# PCBPayloadV7.net
KiCad netlist of a schematic drawn in EAGLE
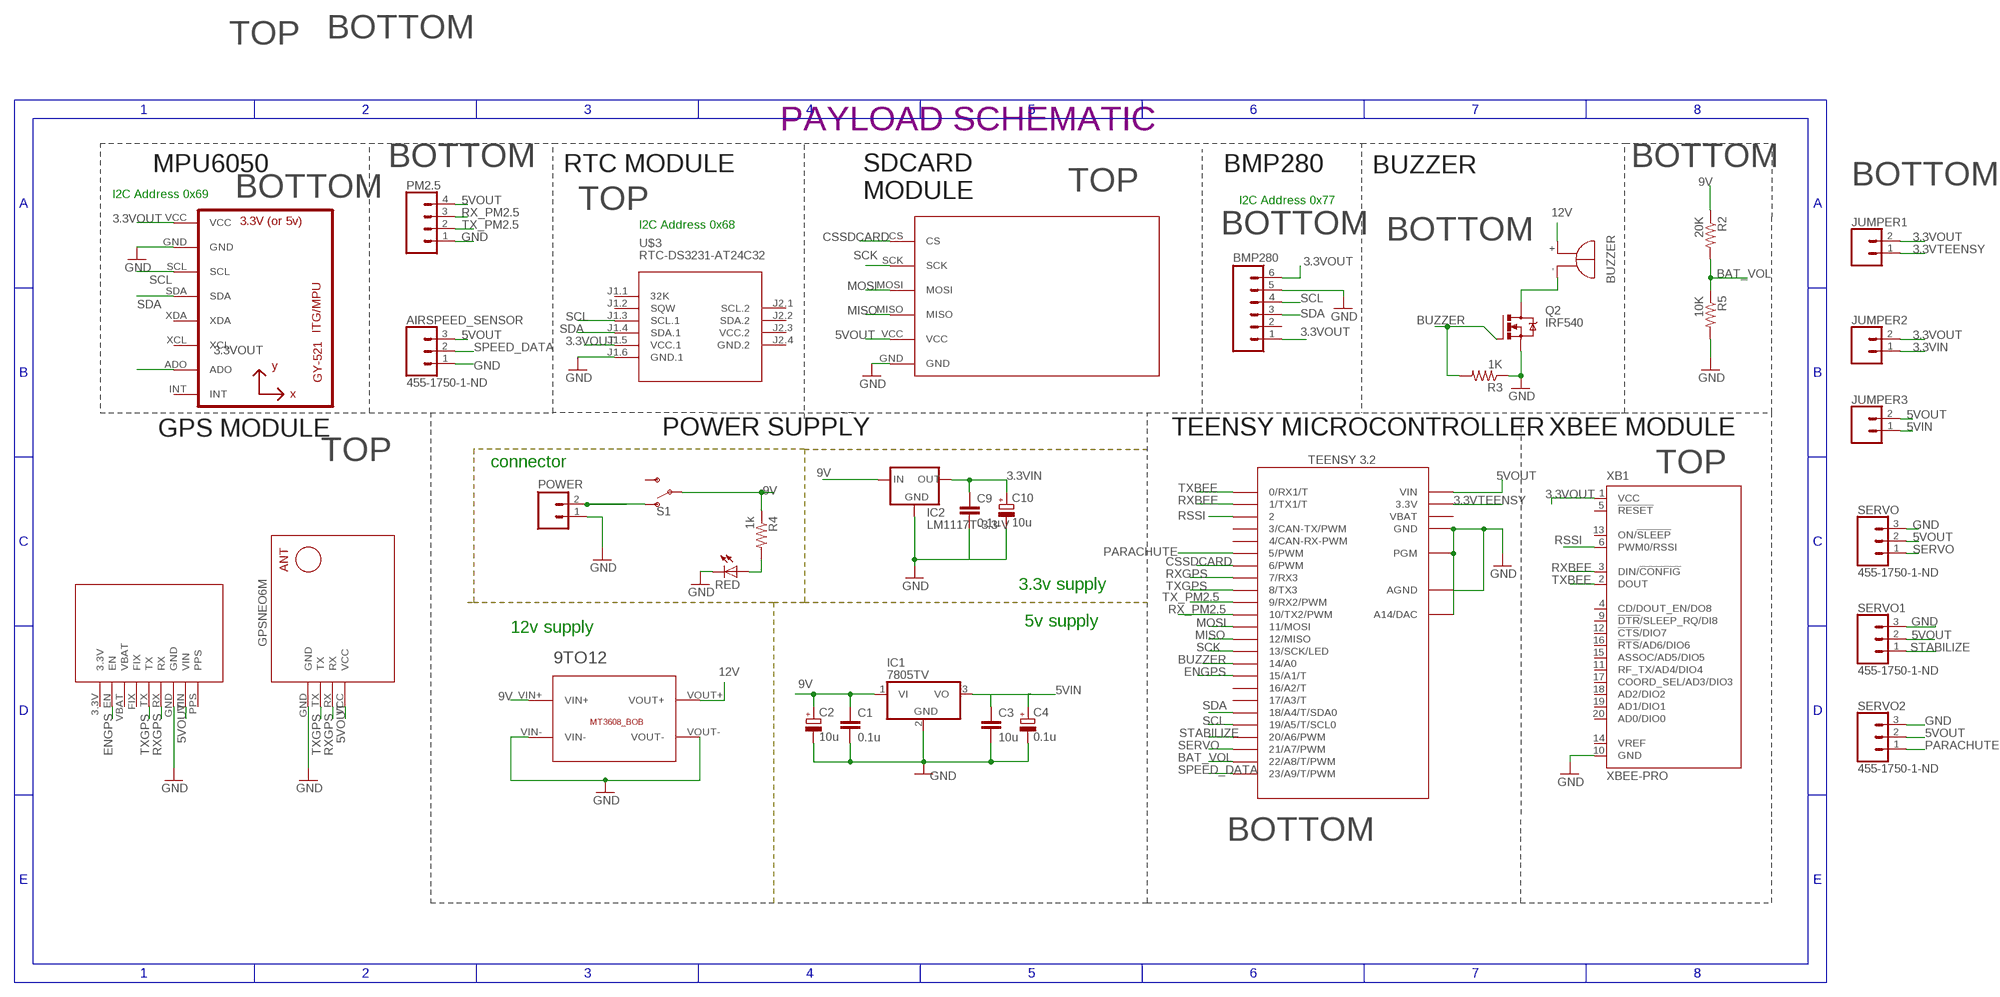
[diagram p0: schematic, sheet 1]

(export (version "E")
  (design (tool "Eeschema 10.0.6"))
  (components
    (comp (ref "9TO12")
      (value "BREAKOUTS_MT3608_BOB")
      (footprint "eagle-import:BREAKOUTS_MT3608_BOB")
      (libsource (lib "eagle-import") (part "BREAKOUTS_MT3608_BOB"))
    )
    (comp (ref "AIRSPEED_SENSOR")
      (value "455-1750-1-ND")
      (footprint "eagle-import:1X03")
      (libsource (lib "eagle-import") (part "CONN_03"))
    )
    (comp (ref "BMP280")
      (value "M06")
      (footprint "eagle-import:06P")
      (libsource (lib "eagle-import") (part "M06"))
    )
    (comp (ref "C1")
      (value "0.1u")
      (footprint "eagle-import:C025-025X050")
      (libsource (lib "eagle-import") (part "C-EU025-025X050"))
    )
    (comp (ref "C2")
      (value "10u")
      (footprint "eagle-import:E2,5-6")
      (libsource (lib "eagle-import") (part "CPOL-EUE2.5-6"))
    )
    (comp (ref "C3")
      (value "10u")
      (footprint "eagle-import:C025-025X050")
      (libsource (lib "eagle-import") (part "C-EU025-025X050"))
    )
    (comp (ref "C4")
      (value "0.1u")
      (footprint "eagle-import:E2,5-6")
      (libsource (lib "eagle-import") (part "CPOL-EUE2.5-6"))
    )
    (comp (ref "C9")
      (value "0.1u")
      (footprint "eagle-import:C025-025X050")
      (libsource (lib "eagle-import") (part "C-EU025-025X050"))
    )
    (comp (ref "C10")
      (value "10u")
      (footprint "eagle-import:E2,5-6")
      (libsource (lib "eagle-import") (part "CPOL-EUE2.5-6"))
    )
    (comp (ref "IC1")
      (value "7805TV")
      (footprint "eagle-import:TO220V")
      (libsource (lib "eagle-import") (part "78TV05"))
    )
    (comp (ref "IC2")
      (value "LM1117T-3.3-V")
      (footprint "eagle-import:TO220V")
      (libsource (lib "eagle-import") (part "LM1117T--V3.3"))
    )
    (comp (ref "JUMPER1")
      (value "CONN_02")
      (footprint "eagle-import:1X02")
      (libsource (lib "eagle-import") (part "CONN_02"))
    )
    (comp (ref "JUMPER2")
      (value "CONN_02")
      (footprint "eagle-import:1X02")
      (libsource (lib "eagle-import") (part "CONN_02"))
    )
    (comp (ref "JUMPER3")
      (value "CONN_02")
      (footprint "eagle-import:1X02")
      (libsource (lib "eagle-import") (part "CONN_02"))
    )
    (comp (ref "PM2.5")
      (value "CONN_04")
      (footprint "eagle-import:1X04")
      (libsource (lib "eagle-import") (part "CONN_04"))
    )
    (comp (ref "POWER")
      (value "CEDT_JANUARY_2015_V5_M02")
      (footprint "eagle-import:CEDT_JANUARY_2015_V5_02P")
      (libsource (lib "eagle-import") (part "CEDT_JANUARY_2015_V5_M02"))
    )
    (comp (ref "Q2")
      (value "IRF540")
      (footprint "eagle-import:TO220BV")
      (libsource (lib "eagle-import") (part "IRF540"))
    )
    (comp (ref "R2")
      (value "20K")
      (footprint "eagle-import:0204_7")
      (libsource (lib "eagle-import") (part "R-US_0204/7"))
    )
    (comp (ref "R3")
      (value "1K")
      (footprint "eagle-import:0204_7")
      (libsource (lib "eagle-import") (part "R-US_0204/7"))
    )
    (comp (ref "R4")
      (value "1k")
      (footprint "eagle-import:0204_7")
      (libsource (lib "eagle-import") (part "R-US_0204/7"))
    )
    (comp (ref "R5")
      (value "10K")
      (footprint "eagle-import:0204_7")
      (libsource (lib "eagle-import") (part "R-US_0204/7"))
    )
    (comp (ref "RED")
      (value "red")
      (footprint "eagle-import:LED3MM")
      (libsource (lib "eagle-import") (part "LED3MM"))
    )
    (comp (ref "S1")
      (value "SWITCH-SPDT-PTH-11.6X4.0MM")
      (footprint "eagle-import:SWITCH_SPDT_PTH_11.6X4.0MM")
      (libsource (lib "eagle-import") (part "SWITCH-SPDT-PTH-11.6X4.0MM"))
    )
    (comp (ref "SERVO")
      (value "455-1750-1-ND")
      (footprint "eagle-import:1X03")
      (libsource (lib "eagle-import") (part "CONN_03"))
    )
    (comp (ref "SERVO1")
      (value "455-1750-1-ND")
      (footprint "eagle-import:1X03")
      (libsource (lib "eagle-import") (part "CONN_03"))
    )
    (comp (ref "SERVO2")
      (value "455-1750-1-ND")
      (footprint "eagle-import:1X03")
      (libsource (lib "eagle-import") (part "CONN_03"))
    )
    (comp (ref "SG1")
      (value "BUZZER_EB2209A")
      (footprint "eagle-import:BUZZER_EB2209A")
      (libsource (lib "eagle-import") (part "BUZZER_EB2209A"))
    )
    (comp (ref "U$1")
      (value "GPS-RECEIVER-NEO6M")
      (footprint "eagle-import:GPS-RECEIVER-NEO6M")
      (libsource (lib "eagle-import") (part "GPS-RECEIVER-NEO6M"))
    )
    (comp (ref "U$2")
      (value "TEENSY_3.1-3.2_OUTER_ROW")
      (footprint "eagle-import:TEENSY_3.0-3.2&LC_OUTER_ROW")
      (libsource (lib "eagle-import") (part "TEENSY_3.1-3.2_OUTER_ROW"))
    )
    (comp (ref "U$3")
      (value "RTC-DS3231-AT24C32")
      (footprint "eagle-import:RTC-DS3231-AT24C32")
      (libsource (lib "eagle-import") (part "RTC-DS3231-AT24C32"))
    )
    (comp (ref "U$4")
      (value "ADAFRUIT_GPS")
      (footprint "eagle-import:ADAFRUIT_GPS")
      (libsource (lib "eagle-import") (part "ADAFRUIT_GPS"))
    )
    (comp (ref "U$5")
      (value "SDCARD")
      (footprint "eagle-import:M0SDCARDMODULE")
      (libsource (lib "eagle-import") (part "SDCARD"))
    )
    (comp (ref "U1")
      (value "GY-521MPU6050")
      (footprint "eagle-import:GY-521")
      (libsource (lib "eagle-import") (part "GY-521MPU6050"))
    )
    (comp (ref "XB1")
      (value "XBEE-PRO")
      (footprint "eagle-import:XBEE-PRO")
      (fields (field (name "MPN") "XBP24-AWI-001"))
      (libsource (lib "eagle-import") (part "XBEE-PRO"))
    )
  )
  (nets
    (net (code "1") (name "/3.3VIN") (class "Default")
      (node (ref "C10") (pin "+") (pinfunction "+_+") (pintype "passive"))
      (node (ref "C9") (pin "1") (pinfunction "1_1") (pintype "passive"))
      (node (ref "IC2") (pin "2") (pinfunction "OUT_2") (pintype "passive"))
      (node (ref "JUMPER2") (pin "1") (pinfunction "1_1") (pintype "passive"))
    )
    (net (code "2") (name "/3.3VOUT") (class "Default")
      (node (ref "BMP280") (pin "1") (pinfunction "1_1") (pintype "passive"))
      (node (ref "BMP280") (pin "6") (pinfunction "6_6") (pintype "passive"))
      (node (ref "JUMPER1") (pin "2") (pinfunction "2_2") (pintype "passive"))
      (node (ref "JUMPER2") (pin "2") (pinfunction "2_2") (pintype "passive"))
      (node (ref "U$3") (pin "J1.5") (pinfunction "VCC.1_J1.5") (pintype "power_in"))
      (node (ref "U1") (pin "ADO") (pinfunction "ADO_ADO") (pintype "bidirectional"))
      (node (ref "U1") (pin "VCC") (pinfunction "VCC_VCC") (pintype "bidirectional"))
      (node (ref "XB1") (pin "1") (pinfunction "VCC_1") (pintype "power_in"))
    )
    (net (code "3") (name "/3.3VTEENSY") (class "Default")
      (node (ref "JUMPER1") (pin "1") (pinfunction "1_1") (pintype "passive"))
      (node (ref "U$2") (pin "3.3V") (pinfunction "3.3V_3.3V") (pintype "power_in"))
      (node (ref "U$2") (pin "3.3V1") (pinfunction "3.3V_3.3V1") (pintype "power_in"))
    )
    (net (code "4") (name "/5VIN") (class "Default")
      (node (ref "C3") (pin "1") (pinfunction "1_1") (pintype "passive"))
      (node (ref "C4") (pin "+") (pinfunction "+_+") (pintype "passive"))
      (node (ref "IC1") (pin "3") (pinfunction "VO_3") (pintype "passive"))
      (node (ref "JUMPER3") (pin "1") (pinfunction "1_1") (pintype "passive"))
    )
    (net (code "5") (name "/5VOUT") (class "Default")
      (node (ref "AIRSPEED_SENSOR") (pin "3") (pinfunction "3_3") (pintype "passive"))
      (node (ref "JUMPER3") (pin "2") (pinfunction "2_2") (pintype "passive"))
      (node (ref "PM2.5") (pin "4") (pinfunction "4_4") (pintype "passive"))
      (node (ref "SERVO") (pin "2") (pinfunction "2_2") (pintype "passive"))
      (node (ref "SERVO1") (pin "2") (pinfunction "2_2") (pintype "passive"))
      (node (ref "SERVO2") (pin "2") (pinfunction "2_2") (pintype "passive"))
      (node (ref "U$1") (pin "VCC") (pinfunction "VCC_VCC") (pintype "power_in"))
      (node (ref "U$2") (pin "VIN") (pinfunction "VIN_VIN") (pintype "power_in"))
      (node (ref "U$4") (pin "VIN") (pinfunction "VIN_VIN") (pintype "bidirectional"))
      (node (ref "U$5") (pin "VCC") (pinfunction "VCC_VCC") (pintype "bidirectional"))
    )
    (net (code "6") (name "/9V") (class "Default")
      (node (ref "9TO12") (pin "VIN+") (pinfunction "VIN+_VIN+") (pintype "bidirectional"))
      (node (ref "C1") (pin "1") (pinfunction "1_1") (pintype "passive"))
      (node (ref "C2") (pin "+") (pinfunction "+_+") (pintype "passive"))
      (node (ref "IC1") (pin "1") (pinfunction "VI_1") (pintype "input"))
      (node (ref "IC2") (pin "3") (pinfunction "IN_3") (pintype "input"))
      (node (ref "R2") (pin "1") (pinfunction "1_1") (pintype "passive"))
      (node (ref "R4") (pin "1") (pinfunction "1_1") (pintype "passive"))
      (node (ref "S1") (pin "2") (pinfunction "P_2") (pintype "passive"))
    )
    (net (code "7") (name "/12V") (class "Default")
      (node (ref "9TO12") (pin "VOUT+") (pinfunction "VOUT+_VOUT+") (pintype "bidirectional"))
      (node (ref "SG1") (pin "+") (pinfunction "+_+") (pintype "passive"))
    )
    (net (code "8") (name "/BAT_VOL") (class "Default")
      (node (ref "R2") (pin "2") (pinfunction "2_2") (pintype "passive"))
      (node (ref "R5") (pin "1") (pinfunction "1_1") (pintype "passive"))
      (node (ref "U$2") (pin "22/A8") (pinfunction "22/A8/T/PWM_22/A8") (pintype "bidirectional"))
    )
    (net (code "9") (name "/BUZZER") (class "Default")
      (node (ref "Q2") (pin "G") (pinfunction "G_G") (pintype "passive"))
      (node (ref "R3") (pin "2") (pinfunction "2_2") (pintype "passive"))
      (node (ref "U$2") (pin "14/A0") (pinfunction "14/A0_14/A0") (pintype "bidirectional"))
    )
    (net (code "10") (name "/CSSDCARD") (class "Default")
      (node (ref "U$2") (pin "6") (pinfunction "6/PWM_6") (pintype "bidirectional"))
      (node (ref "U$5") (pin "CS") (pinfunction "CS_CS") (pintype "bidirectional"))
    )
    (net (code "11") (name "/ENGPS") (class "Default")
      (node (ref "U$2") (pin "15/A1") (pinfunction "15/A1/T_15/A1") (pintype "bidirectional"))
      (node (ref "U$4") (pin "EN") (pinfunction "EN_EN") (pintype "bidirectional"))
    )
    (net (code "12") (name "/GND.2") (class "Default")
      (node (ref "U$3") (pin "J2.4") (pinfunction "GND.2_J2.4") (pintype "power_in"))
    )
    (net (code "13") (name "/MISO") (class "Default")
      (node (ref "U$2") (pin "12") (pinfunction "12/MISO_12") (pintype "bidirectional"))
      (node (ref "U$5") (pin "MISO") (pinfunction "MISO_MISO") (pintype "bidirectional"))
    )
    (net (code "14") (name "/MOSI") (class "Default")
      (node (ref "U$2") (pin "11") (pinfunction "11/MOSI_11") (pintype "bidirectional"))
      (node (ref "U$5") (pin "MOSI") (pinfunction "MOSI_MOSI") (pintype "bidirectional"))
    )
    (net (code "15") (name "/PARACHUTE") (class "Default")
      (node (ref "SERVO2") (pin "1") (pinfunction "1_1") (pintype "passive"))
      (node (ref "U$2") (pin "5") (pinfunction "5/PWM_5") (pintype "bidirectional"))
    )
    (net (code "16") (name "/RSSI") (class "Default")
      (node (ref "U$2") (pin "2") (pinfunction "2_2") (pintype "bidirectional"))
      (node (ref "XB1") (pin "6") (pinfunction "PWM0/RSSI_6") (pintype "output"))
    )
    (net (code "17") (name "/RXBEE") (class "Default")
      (node (ref "U$2") (pin "1") (pinfunction "1/TX1/T_1") (pintype "bidirectional"))
      (node (ref "XB1") (pin "3") (pinfunction "DIN/~{CONFIG}_3") (pintype "input"))
    )
    (net (code "18") (name "/RXGPS") (class "Default")
      (node (ref "U$1") (pin "RX") (pinfunction "RX_RX") (pintype "bidirectional"))
      (node (ref "U$2") (pin "7") (pinfunction "7/RX3_7") (pintype "bidirectional"))
      (node (ref "U$4") (pin "RX") (pinfunction "RX_RX") (pintype "bidirectional"))
    )
    (net (code "19") (name "/RX_PM2.5") (class "Default")
      (node (ref "PM2.5") (pin "3") (pinfunction "3_3") (pintype "passive"))
      (node (ref "U$2") (pin "10") (pinfunction "10/TX2/PWM_10") (pintype "bidirectional"))
    )
    (net (code "20") (name "/SCK") (class "Default")
      (node (ref "U$2") (pin "13") (pinfunction "13/SCK/LED_13") (pintype "bidirectional"))
      (node (ref "U$5") (pin "SCK") (pinfunction "SCK_SCK") (pintype "bidirectional"))
    )
    (net (code "21") (name "/SCL") (class "Default")
      (node (ref "BMP280") (pin "4") (pinfunction "4_4") (pintype "passive"))
      (node (ref "U$2") (pin "19/A5") (pinfunction "19/A5/T/SCL0_19/A5") (pintype "bidirectional"))
      (node (ref "U$3") (pin "J1.3") (pinfunction "SCL.1_J1.3") (pintype "bidirectional"))
      (node (ref "U1") (pin "SCL") (pinfunction "SCL_SCL") (pintype "bidirectional"))
    )
    (net (code "22") (name "/SDA") (class "Default")
      (node (ref "BMP280") (pin "3") (pinfunction "3_3") (pintype "passive"))
      (node (ref "U$2") (pin "18/A4") (pinfunction "18/A4/T/SDA0_18/A4") (pintype "bidirectional"))
      (node (ref "U$3") (pin "J1.4") (pinfunction "SDA.1_J1.4") (pintype "bidirectional"))
      (node (ref "U1") (pin "SDA") (pinfunction "SDA_SDA") (pintype "bidirectional"))
    )
    (net (code "23") (name "/SERVO") (class "Default")
      (node (ref "SERVO") (pin "1") (pinfunction "1_1") (pintype "passive"))
      (node (ref "U$2") (pin "21/A7") (pinfunction "21/A7/PWM_21/A7") (pintype "bidirectional"))
    )
    (net (code "24") (name "/SPEED_DATA") (class "Default")
      (node (ref "AIRSPEED_SENSOR") (pin "2") (pinfunction "2_2") (pintype "passive"))
      (node (ref "U$2") (pin "23/A9") (pinfunction "23/A9/T/PWM_23/A9") (pintype "bidirectional"))
    )
    (net (code "25") (name "/STABILIZE") (class "Default")
      (node (ref "SERVO1") (pin "1") (pinfunction "1_1") (pintype "passive"))
      (node (ref "U$2") (pin "20/A6") (pinfunction "20/A6/PWM_20/A6") (pintype "bidirectional"))
    )
    (net (code "26") (name "/TXBEE") (class "Default")
      (node (ref "U$2") (pin "0") (pinfunction "0/RX1/T_0") (pintype "bidirectional"))
      (node (ref "XB1") (pin "2") (pinfunction "DOUT_2") (pintype "output"))
    )
    (net (code "27") (name "/TXGPS") (class "Default")
      (node (ref "U$1") (pin "TX") (pinfunction "TX_TX") (pintype "bidirectional"))
      (node (ref "U$2") (pin "8") (pinfunction "8/TX3_8") (pintype "bidirectional"))
      (node (ref "U$4") (pin "TX") (pinfunction "TX_TX") (pintype "bidirectional"))
    )
    (net (code "28") (name "/TX_PM2.5") (class "Default")
      (node (ref "PM2.5") (pin "2") (pinfunction "2_2") (pintype "passive"))
      (node (ref "U$2") (pin "9") (pinfunction "9/RX2/PWM_9") (pintype "bidirectional"))
    )
    (net (code "29") (name "/VBAT") (class "Default")
      (node (ref "U$2") (pin "VBAT") (pinfunction "VBAT_VBAT") (pintype "power_in"))
    )
    (net (code "30") (name "/VCC.2") (class "Default")
      (node (ref "U$3") (pin "J2.3") (pinfunction "VCC.2_J2.3") (pintype "power_in"))
    )
    (net (code "31") (name "GND") (class "Default")
      (node (ref "9TO12") (pin "VIN-") (pinfunction "VIN-_VIN-") (pintype "bidirectional"))
      (node (ref "9TO12") (pin "VOUT-") (pinfunction "VOUT-_VOUT-") (pintype "bidirectional"))
      (node (ref "AIRSPEED_SENSOR") (pin "1") (pinfunction "1_1") (pintype "passive"))
      (node (ref "BMP280") (pin "5") (pinfunction "5_5") (pintype "passive"))
      (node (ref "C1") (pin "2") (pinfunction "2_2") (pintype "passive"))
      (node (ref "C10") (pin "-") (pinfunction "-_-") (pintype "passive"))
      (node (ref "C2") (pin "-") (pinfunction "-_-") (pintype "passive"))
      (node (ref "C3") (pin "2") (pinfunction "2_2") (pintype "passive"))
      (node (ref "C4") (pin "-") (pinfunction "-_-") (pintype "passive"))
      (node (ref "C9") (pin "2") (pinfunction "2_2") (pintype "passive"))
      (node (ref "IC1") (pin "2") (pinfunction "GND_2") (pintype "passive"))
      (node (ref "IC2") (pin "1") (pinfunction "GND_1") (pintype "input"))
      (node (ref "PM2.5") (pin "1") (pinfunction "1_1") (pintype "passive"))
      (node (ref "POWER") (pin "1") (pinfunction "1_1") (pintype "passive"))
      (node (ref "Q2") (pin "S") (pinfunction "S_S") (pintype "passive"))
      (node (ref "R3") (pin "1") (pinfunction "1_1") (pintype "passive"))
      (node (ref "R5") (pin "2") (pinfunction "2_2") (pintype "passive"))
      (node (ref "RED") (pin "K") (pinfunction "C_K") (pintype "passive"))
      (node (ref "SERVO") (pin "3") (pinfunction "3_3") (pintype "passive"))
      (node (ref "SERVO1") (pin "3") (pinfunction "3_3") (pintype "passive"))
      (node (ref "SERVO2") (pin "3") (pinfunction "3_3") (pintype "passive"))
      (node (ref "U$1") (pin "GND") (pinfunction "GND_GND") (pintype "bidirectional"))
      (node (ref "U$2") (pin "AGND") (pinfunction "AGND_AGND") (pintype "power_in"))
      (node (ref "U$2") (pin "GND") (pinfunction "GND_GND") (pintype "power_in"))
      (node (ref "U$2") (pin "GND1") (pinfunction "GND_GND1") (pintype "power_in"))
      (node (ref "U$2") (pin "PGM") (pinfunction "PGM_PGM") (pintype "bidirectional"))
      (node (ref "U$2") (pin "RESET/DAC") (pinfunction "A14/DAC_RESET/DAC") (pintype "bidirectional"))
      (node (ref "U$3") (pin "J1.6") (pinfunction "GND.1_J1.6") (pintype "power_in"))
      (node (ref "U$4") (pin "GND") (pinfunction "GND_GND") (pintype "bidirectional"))
      (node (ref "U$5") (pin "GND") (pinfunction "GND_GND") (pintype "bidirectional"))
      (node (ref "U1") (pin "GND") (pinfunction "GND_GND") (pintype "bidirectional"))
      (node (ref "XB1") (pin "10") (pinfunction "GND_10") (pintype "power_in"))
    )
    (net (code "32") (name "Net-(Q2-PadD)") (class "Default")
      (node (ref "Q2") (pin "D") (pinfunction "D_D") (pintype "passive"))
      (node (ref "SG1") (pin "-") (pinfunction "-_-") (pintype "passive"))
    )
    (net (code "33") (name "Net-(R4-Pad2)") (class "Default")
      (node (ref "R4") (pin "2") (pinfunction "2_2") (pintype "passive"))
      (node (ref "RED") (pin "A") (pinfunction "A_A") (pintype "passive"))
    )
    (net (code "34") (name "Net-(S1-O)") (class "Default")
      (node (ref "POWER") (pin "2") (pinfunction "2_2") (pintype "passive"))
      (node (ref "S1") (pin "1") (pinfunction "O_1") (pintype "passive"))
    )
    (net (code "35") (name "unconnected-(BMP280-Pad2)") (class "Default")
      (node (ref "BMP280") (pin "2") (pinfunction "2_2") (pintype "passive"))
    )
    (net (code "36") (name "unconnected-(S1-S-Pad3)") (class "Default")
      (node (ref "S1") (pin "3") (pinfunction "S_3") (pintype "passive"))
    )
    (net (code "37") (name "unconnected-(U$2-3{slash}CAN-TX{slash}PWM-Pad3)") (class "Default")
      (node (ref "U$2") (pin "3") (pinfunction "3/CAN-TX/PWM_3") (pintype "bidirectional"))
    )
    (net (code "38") (name "unconnected-(U$2-4{slash}CAN-RX-PWM-Pad4)") (class "Default")
      (node (ref "U$2") (pin "4") (pinfunction "4/CAN-RX-PWM_4") (pintype "bidirectional"))
    )
    (net (code "39") (name "unconnected-(U$2-16{slash}A2{slash}T-Pad16{slash}A2)") (class "Default")
      (node (ref "U$2") (pin "16/A2") (pinfunction "16/A2/T_16/A2") (pintype "bidirectional"))
    )
    (net (code "40") (name "unconnected-(U$2-17{slash}A3{slash}T-Pad17{slash}A3)") (class "Default")
      (node (ref "U$2") (pin "17/A3") (pinfunction "17/A3/T_17/A3") (pintype "bidirectional"))
    )
    (net (code "41") (name "unconnected-(U$3-32K-PadJ1.1)") (class "Default")
      (node (ref "U$3") (pin "J1.1") (pinfunction "32K_J1.1") (pintype "bidirectional"))
    )
    (net (code "42") (name "unconnected-(U$3-SCL.2-PadJ2.1)") (class "Default")
      (node (ref "U$3") (pin "J2.1") (pinfunction "SCL.2_J2.1") (pintype "bidirectional"))
    )
    (net (code "43") (name "unconnected-(U$3-SDA.2-PadJ2.2)") (class "Default")
      (node (ref "U$3") (pin "J2.2") (pinfunction "SDA.2_J2.2") (pintype "bidirectional"))
    )
    (net (code "44") (name "unconnected-(U$3-SQW-PadJ1.2)") (class "Default")
      (node (ref "U$3") (pin "J1.2") (pinfunction "SQW_J1.2") (pintype "bidirectional"))
    )
    (net (code "45") (name "unconnected-(U$4-Pad3.3V)") (class "Default")
      (node (ref "U$4") (pin "3.3V") (pinfunction "3.3V_3.3V") (pintype "bidirectional"))
    )
    (net (code "46") (name "unconnected-(U$4-PadFIX)") (class "Default")
      (node (ref "U$4") (pin "FIX") (pinfunction "FIX_FIX") (pintype "bidirectional"))
    )
    (net (code "47") (name "unconnected-(U$4-PadPPS)") (class "Default")
      (node (ref "U$4") (pin "PPS") (pinfunction "PPS_PPS") (pintype "bidirectional"))
    )
    (net (code "48") (name "unconnected-(U$4-PadVBAT)") (class "Default")
      (node (ref "U$4") (pin "VBAT") (pinfunction "VBAT_VBAT") (pintype "bidirectional"))
    )
    (net (code "49") (name "unconnected-(U1-PadINT)") (class "Default")
      (node (ref "U1") (pin "INT") (pinfunction "INT_INT") (pintype "bidirectional"))
    )
    (net (code "50") (name "unconnected-(U1-PadXCL)") (class "Default")
      (node (ref "U1") (pin "XCL") (pinfunction "XCL_XCL") (pintype "bidirectional"))
    )
    (net (code "51") (name "unconnected-(U1-PadXDA)") (class "Default")
      (node (ref "U1") (pin "XDA") (pinfunction "XDA_XDA") (pintype "bidirectional"))
    )
    (net (code "52") (name "unconnected-(XB1-AD0{slash}DIO0-Pad20)") (class "Default")
      (node (ref "XB1") (pin "20") (pinfunction "AD0/DIO0_20") (pintype "bidirectional"))
    )
    (net (code "53") (name "unconnected-(XB1-AD1{slash}DIO1-Pad19)") (class "Default")
      (node (ref "XB1") (pin "19") (pinfunction "AD1/DIO1_19") (pintype "bidirectional"))
    )
    (net (code "54") (name "unconnected-(XB1-AD2{slash}DIO2-Pad18)") (class "Default")
      (node (ref "XB1") (pin "18") (pinfunction "AD2/DIO2_18") (pintype "bidirectional"))
    )
    (net (code "55") (name "unconnected-(XB1-ASSOC{slash}AD5{slash}DIO5-Pad15)") (class "Default")
      (node (ref "XB1") (pin "15") (pinfunction "ASSOC/AD5/DIO5_15") (pintype "bidirectional"))
    )
    (net (code "56") (name "unconnected-(XB1-CD{slash}DOUT_EN{slash}DO8-Pad4)") (class "Default")
      (node (ref "XB1") (pin "4") (pinfunction "CD/DOUT_EN/DO8_4") (pintype "output"))
    )
    (net (code "57") (name "unconnected-(XB1-COORD_SEL{slash}AD3{slash}DIO3-Pad17)") (class "Default")
      (node (ref "XB1") (pin "17") (pinfunction "COORD_SEL/AD3/DIO3_17") (pintype "bidirectional"))
    )
    (net (code "58") (name "unconnected-(XB1-ON{slash}~{SLEEP}-Pad13)") (class "Default")
      (node (ref "XB1") (pin "13") (pinfunction "ON/~{SLEEP}_13") (pintype "output"))
    )
    (net (code "59") (name "unconnected-(XB1-RF_TX{slash}AD4{slash}DIO4-Pad11)") (class "Default")
      (node (ref "XB1") (pin "11") (pinfunction "RF_TX/AD4/DIO4_11") (pintype "bidirectional"))
    )
    (net (code "60") (name "unconnected-(XB1-VREF-Pad14)") (class "Default")
      (node (ref "XB1") (pin "14") (pinfunction "VREF_14") (pintype "input"))
    )
    (net (code "61") (name "unconnected-(XB1-~{CTS}{slash}DIO7-Pad12)") (class "Default")
      (node (ref "XB1") (pin "12") (pinfunction "~{CTS}/DIO7_12") (pintype "bidirectional"))
    )
    (net (code "62") (name "unconnected-(XB1-~{DTR}{slash}SLEEP_RQ{slash}DI8-Pad9)") (class "Default")
      (node (ref "XB1") (pin "9") (pinfunction "~{DTR}/SLEEP_RQ/DI8_9") (pintype "bidirectional"))
    )
    (net (code "63") (name "unconnected-(XB1-~{RESET}-Pad5)") (class "Default")
      (node (ref "XB1") (pin "5") (pinfunction "~{RESET}_5") (pintype "input"))
    )
    (net (code "64") (name "unconnected-(XB1-~{RTS}{slash}AD6{slash}DIO6-Pad16)") (class "Default")
      (node (ref "XB1") (pin "16") (pinfunction "~{RTS}/AD6/DIO6_16") (pintype "bidirectional"))
    )
  )
)
